# teensyShield1_9.net
KiCad netlist of a schematic drawn in EAGLE
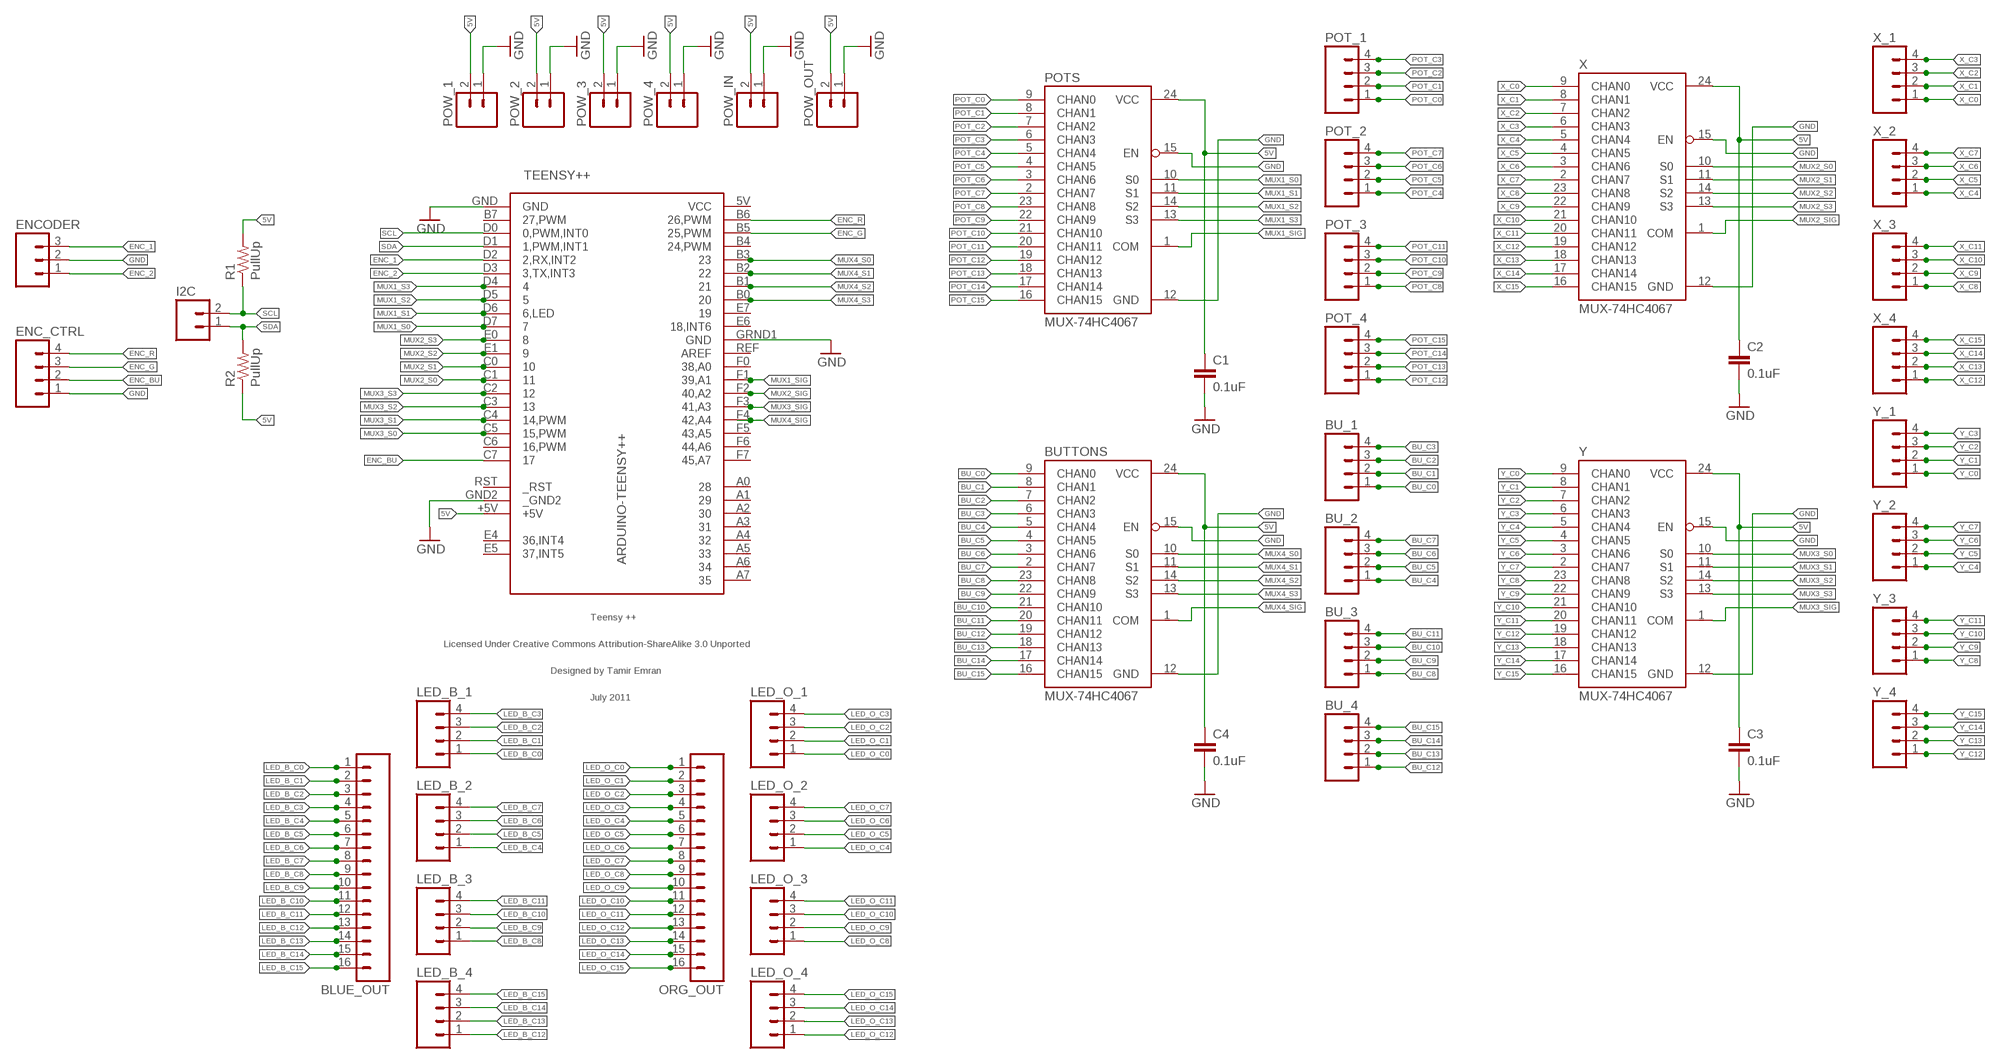
[diagram p0: schematic, sheet 1]

(export (version "E")
  (design (tool "Eeschema 10.0.6"))
  (components
    (comp (ref "BLUE_OUT")
      (value "M161X16_NO_SILK")
      (footprint "eagle-import:1X16_NO_SILK")
      (libsource (lib "eagle-import") (part "M161X16_NO_SILK"))
    )
    (comp (ref "BUTTONS")
      (value "MUX-74HC4067")
      (footprint "eagle-import:SSOP24")
      (libsource (lib "eagle-import") (part "MUX-74HC4067SMD"))
    )
    (comp (ref "BU_1")
      (value "M04NO_SILK_ALL_ROUND")
      (footprint "eagle-import:1X04_NO_SILK_ALL_ROUND")
      (libsource (lib "eagle-import") (part "M04NO_SILK_ALL_ROUND"))
    )
    (comp (ref "BU_2")
      (value "M04NO_SILK_ALL_ROUND")
      (footprint "eagle-import:1X04_NO_SILK_ALL_ROUND")
      (libsource (lib "eagle-import") (part "M04NO_SILK_ALL_ROUND"))
    )
    (comp (ref "BU_3")
      (value "M04NO_SILK_ALL_ROUND")
      (footprint "eagle-import:1X04_NO_SILK_ALL_ROUND")
      (libsource (lib "eagle-import") (part "M04NO_SILK_ALL_ROUND"))
    )
    (comp (ref "BU_4")
      (value "M04NO_SILK_ALL_ROUND")
      (footprint "eagle-import:1X04_NO_SILK_ALL_ROUND")
      (libsource (lib "eagle-import") (part "M04NO_SILK_ALL_ROUND"))
    )
    (comp (ref "C1")
      (value "0.1uF")
      (footprint "eagle-import:0603")
      (libsource (lib "eagle-import") (part "CAP0603"))
    )
    (comp (ref "C2")
      (value "0.1uF")
      (footprint "eagle-import:0603")
      (libsource (lib "eagle-import") (part "CAP0603"))
    )
    (comp (ref "C3")
      (value "0.1uF")
      (footprint "eagle-import:0603")
      (libsource (lib "eagle-import") (part "CAP0603"))
    )
    (comp (ref "C4")
      (value "0.1uF")
      (footprint "eagle-import:0603")
      (libsource (lib "eagle-import") (part "CAP0603"))
    )
    (comp (ref "ENCODER")
      (value "M031X03_NO_SILK")
      (footprint "eagle-import:1X03_NO_SILK")
      (libsource (lib "eagle-import") (part "M031X03_NO_SILK"))
    )
    (comp (ref "ENC_CTRL")
      (value "M041X04_NO_SILK")
      (footprint "eagle-import:1X04_NO_SILK")
      (libsource (lib "eagle-import") (part "M041X04_NO_SILK"))
    )
    (comp (ref "I2C")
      (value "M02LOCK")
      (footprint "eagle-import:1X02_LOCK")
      (libsource (lib "eagle-import") (part "M02LOCK"))
    )
    (comp (ref "LED_B_1")
      (value "M04NO_SILK_ALL_ROUND")
      (footprint "eagle-import:1X04_NO_SILK_ALL_ROUND")
      (libsource (lib "eagle-import") (part "M04NO_SILK_ALL_ROUND"))
    )
    (comp (ref "LED_B_2")
      (value "M04NO_SILK_ALL_ROUND")
      (footprint "eagle-import:1X04_NO_SILK_ALL_ROUND")
      (libsource (lib "eagle-import") (part "M04NO_SILK_ALL_ROUND"))
    )
    (comp (ref "LED_B_3")
      (value "M04NO_SILK_ALL_ROUND")
      (footprint "eagle-import:1X04_NO_SILK_ALL_ROUND")
      (libsource (lib "eagle-import") (part "M04NO_SILK_ALL_ROUND"))
    )
    (comp (ref "LED_B_4")
      (value "M04NO_SILK_ALL_ROUND")
      (footprint "eagle-import:1X04_NO_SILK_ALL_ROUND")
      (libsource (lib "eagle-import") (part "M04NO_SILK_ALL_ROUND"))
    )
    (comp (ref "LED_O_1")
      (value "M04NO_SILK_ALL_ROUND")
      (footprint "eagle-import:1X04_NO_SILK_ALL_ROUND")
      (libsource (lib "eagle-import") (part "M04NO_SILK_ALL_ROUND"))
    )
    (comp (ref "LED_O_2")
      (value "M04NO_SILK_ALL_ROUND")
      (footprint "eagle-import:1X04_NO_SILK_ALL_ROUND")
      (libsource (lib "eagle-import") (part "M04NO_SILK_ALL_ROUND"))
    )
    (comp (ref "LED_O_3")
      (value "M04NO_SILK_ALL_ROUND")
      (footprint "eagle-import:1X04_NO_SILK_ALL_ROUND")
      (libsource (lib "eagle-import") (part "M04NO_SILK_ALL_ROUND"))
    )
    (comp (ref "LED_O_4")
      (value "M04NO_SILK_ALL_ROUND")
      (footprint "eagle-import:1X04_NO_SILK_ALL_ROUND")
      (libsource (lib "eagle-import") (part "M04NO_SILK_ALL_ROUND"))
    )
    (comp (ref "ORG_OUT")
      (value "M161X16_NO_SILK")
      (footprint "eagle-import:1X16_NO_SILK")
      (libsource (lib "eagle-import") (part "M161X16_NO_SILK"))
    )
    (comp (ref "POTS")
      (value "MUX-74HC4067")
      (footprint "eagle-import:SSOP24")
      (libsource (lib "eagle-import") (part "MUX-74HC4067SMD"))
    )
    (comp (ref "POT_1")
      (value "M04NO_SILK_ALL_ROUND")
      (footprint "eagle-import:1X04_NO_SILK_ALL_ROUND")
      (libsource (lib "eagle-import") (part "M04NO_SILK_ALL_ROUND"))
    )
    (comp (ref "POT_2")
      (value "M04NO_SILK_ALL_ROUND")
      (footprint "eagle-import:1X04_NO_SILK_ALL_ROUND")
      (libsource (lib "eagle-import") (part "M04NO_SILK_ALL_ROUND"))
    )
    (comp (ref "POT_3")
      (value "M04NO_SILK_ALL_ROUND")
      (footprint "eagle-import:1X04_NO_SILK_ALL_ROUND")
      (libsource (lib "eagle-import") (part "M04NO_SILK_ALL_ROUND"))
    )
    (comp (ref "POT_4")
      (value "M04NO_SILK_ALL_ROUND")
      (footprint "eagle-import:1X04_NO_SILK_ALL_ROUND")
      (libsource (lib "eagle-import") (part "M04NO_SILK_ALL_ROUND"))
    )
    (comp (ref "POW_1")
      (value "M02POLAR")
      (footprint "eagle-import:MOLEX-1X2")
      (libsource (lib "eagle-import") (part "M02POLAR"))
    )
    (comp (ref "POW_2")
      (value "M02POLAR")
      (footprint "eagle-import:MOLEX-1X2")
      (libsource (lib "eagle-import") (part "M02POLAR"))
    )
    (comp (ref "POW_3")
      (value "M02POLAR")
      (footprint "eagle-import:MOLEX-1X2")
      (libsource (lib "eagle-import") (part "M02POLAR"))
    )
    (comp (ref "POW_4")
      (value "M02POLAR")
      (footprint "eagle-import:MOLEX-1X2")
      (libsource (lib "eagle-import") (part "M02POLAR"))
    )
    (comp (ref "POW_IN")
      (value "M02POLAR")
      (footprint "eagle-import:MOLEX-1X2")
      (libsource (lib "eagle-import") (part "M02POLAR"))
    )
    (comp (ref "POW_OUT")
      (value "M02POLAR")
      (footprint "eagle-import:MOLEX-1X2")
      (libsource (lib "eagle-import") (part "M02POLAR"))
    )
    (comp (ref "R1")
      (value "PullUp")
      (footprint "eagle-import:AXIAL-0.3")
      (libsource (lib "eagle-import") (part "10KOHM-1/4W5%(PTH)"))
    )
    (comp (ref "R2")
      (value "PullUp")
      (footprint "eagle-import:AXIAL-0.3")
      (libsource (lib "eagle-import") (part "10KOHM-1/4W5%(PTH)"))
    )
    (comp (ref "TEENSY++")
      (value "ARDUINO-TEENSY++")
      (footprint "eagle-import:TEENSY++")
      (libsource (lib "eagle-import") (part "ARDUINO-TEENSY++"))
    )
    (comp (ref "X")
      (value "MUX-74HC4067")
      (footprint "eagle-import:SSOP24")
      (libsource (lib "eagle-import") (part "MUX-74HC4067SMD"))
    )
    (comp (ref "X_1")
      (value "M04NO_SILK_ALL_ROUND")
      (footprint "eagle-import:1X04_NO_SILK_ALL_ROUND")
      (libsource (lib "eagle-import") (part "M04NO_SILK_ALL_ROUND"))
    )
    (comp (ref "X_2")
      (value "M04NO_SILK_ALL_ROUND")
      (footprint "eagle-import:1X04_NO_SILK_ALL_ROUND")
      (libsource (lib "eagle-import") (part "M04NO_SILK_ALL_ROUND"))
    )
    (comp (ref "X_3")
      (value "M04NO_SILK_ALL_ROUND")
      (footprint "eagle-import:1X04_NO_SILK_ALL_ROUND")
      (libsource (lib "eagle-import") (part "M04NO_SILK_ALL_ROUND"))
    )
    (comp (ref "X_4")
      (value "M04NO_SILK_ALL_ROUND")
      (footprint "eagle-import:1X04_NO_SILK_ALL_ROUND")
      (libsource (lib "eagle-import") (part "M04NO_SILK_ALL_ROUND"))
    )
    (comp (ref "Y")
      (value "MUX-74HC4067")
      (footprint "eagle-import:SSOP24")
      (libsource (lib "eagle-import") (part "MUX-74HC4067SMD"))
    )
    (comp (ref "Y_1")
      (value "M04NO_SILK_ALL_ROUND")
      (footprint "eagle-import:1X04_NO_SILK_ALL_ROUND")
      (libsource (lib "eagle-import") (part "M04NO_SILK_ALL_ROUND"))
    )
    (comp (ref "Y_2")
      (value "M04NO_SILK_ALL_ROUND")
      (footprint "eagle-import:1X04_NO_SILK_ALL_ROUND")
      (libsource (lib "eagle-import") (part "M04NO_SILK_ALL_ROUND"))
    )
    (comp (ref "Y_3")
      (value "M04NO_SILK_ALL_ROUND")
      (footprint "eagle-import:1X04_NO_SILK_ALL_ROUND")
      (libsource (lib "eagle-import") (part "M04NO_SILK_ALL_ROUND"))
    )
    (comp (ref "Y_4")
      (value "M04NO_SILK_ALL_ROUND")
      (footprint "eagle-import:1X04_NO_SILK_ALL_ROUND")
      (libsource (lib "eagle-import") (part "M04NO_SILK_ALL_ROUND"))
    )
  )
  (nets
    (net (code "1") (name "/VCC") (class "Default")
      (node (ref "TEENSY++") (pin "5V") (pinfunction "VCC_5V") (pintype "power_in"))
    )
    (net (code "2") (name "5V") (class "Default")
      (node (ref "BUTTONS") (pin "24") (pinfunction "VCC_24") (pintype "bidirectional"))
      (node (ref "C1") (pin "1") (pinfunction "1_1") (pintype "passive"))
      (node (ref "C2") (pin "1") (pinfunction "1_1") (pintype "passive"))
      (node (ref "C3") (pin "1") (pinfunction "1_1") (pintype "passive"))
      (node (ref "C4") (pin "1") (pinfunction "1_1") (pintype "passive"))
      (node (ref "POTS") (pin "24") (pinfunction "VCC_24") (pintype "bidirectional"))
      (node (ref "POW_1") (pin "2") (pinfunction "2_2") (pintype "passive"))
      (node (ref "POW_2") (pin "2") (pinfunction "2_2") (pintype "passive"))
      (node (ref "POW_3") (pin "2") (pinfunction "2_2") (pintype "passive"))
      (node (ref "POW_4") (pin "2") (pinfunction "2_2") (pintype "passive"))
      (node (ref "POW_IN") (pin "2") (pinfunction "2_2") (pintype "passive"))
      (node (ref "POW_OUT") (pin "2") (pinfunction "2_2") (pintype "passive"))
      (node (ref "R1") (pin "P$2") (pinfunction "2_P$2") (pintype "passive"))
      (node (ref "R2") (pin "P$1") (pinfunction "1_P$1") (pintype "passive"))
      (node (ref "TEENSY++") (pin "+5V") (pinfunction "+5V_+5V") (pintype "power_in"))
      (node (ref "X") (pin "24") (pinfunction "VCC_24") (pintype "bidirectional"))
      (node (ref "Y") (pin "24") (pinfunction "VCC_24") (pintype "bidirectional"))
    )
    (net (code "3") (name "BU_C0") (class "Default")
      (node (ref "BUTTONS") (pin "9") (pinfunction "CHAN0_9") (pintype "bidirectional"))
      (node (ref "BU_1") (pin "1") (pinfunction "1_1") (pintype "passive"))
    )
    (net (code "4") (name "BU_C1") (class "Default")
      (node (ref "BUTTONS") (pin "8") (pinfunction "CHAN1_8") (pintype "bidirectional"))
      (node (ref "BU_1") (pin "2") (pinfunction "2_2") (pintype "passive"))
    )
    (net (code "5") (name "BU_C2") (class "Default")
      (node (ref "BUTTONS") (pin "7") (pinfunction "CHAN2_7") (pintype "bidirectional"))
      (node (ref "BU_1") (pin "3") (pinfunction "3_3") (pintype "passive"))
    )
    (net (code "6") (name "BU_C3") (class "Default")
      (node (ref "BUTTONS") (pin "6") (pinfunction "CHAN3_6") (pintype "bidirectional"))
      (node (ref "BU_1") (pin "4") (pinfunction "4_4") (pintype "passive"))
    )
    (net (code "7") (name "BU_C4") (class "Default")
      (node (ref "BUTTONS") (pin "5") (pinfunction "CHAN4_5") (pintype "bidirectional"))
      (node (ref "BU_2") (pin "1") (pinfunction "1_1") (pintype "passive"))
    )
    (net (code "8") (name "BU_C5") (class "Default")
      (node (ref "BUTTONS") (pin "4") (pinfunction "CHAN5_4") (pintype "bidirectional"))
      (node (ref "BU_2") (pin "2") (pinfunction "2_2") (pintype "passive"))
    )
    (net (code "9") (name "BU_C6") (class "Default")
      (node (ref "BUTTONS") (pin "3") (pinfunction "CHAN6_3") (pintype "bidirectional"))
      (node (ref "BU_2") (pin "3") (pinfunction "3_3") (pintype "passive"))
    )
    (net (code "10") (name "BU_C7") (class "Default")
      (node (ref "BUTTONS") (pin "2") (pinfunction "CHAN7_2") (pintype "bidirectional"))
      (node (ref "BU_2") (pin "4") (pinfunction "4_4") (pintype "passive"))
    )
    (net (code "11") (name "BU_C8") (class "Default")
      (node (ref "BUTTONS") (pin "23") (pinfunction "CHAN8_23") (pintype "bidirectional"))
      (node (ref "BU_3") (pin "1") (pinfunction "1_1") (pintype "passive"))
    )
    (net (code "12") (name "BU_C9") (class "Default")
      (node (ref "BUTTONS") (pin "22") (pinfunction "CHAN9_22") (pintype "bidirectional"))
      (node (ref "BU_3") (pin "2") (pinfunction "2_2") (pintype "passive"))
    )
    (net (code "13") (name "BU_C10") (class "Default")
      (node (ref "BUTTONS") (pin "21") (pinfunction "CHAN10_21") (pintype "bidirectional"))
      (node (ref "BU_3") (pin "3") (pinfunction "3_3") (pintype "passive"))
    )
    (net (code "14") (name "BU_C11") (class "Default")
      (node (ref "BUTTONS") (pin "20") (pinfunction "CHAN11_20") (pintype "bidirectional"))
      (node (ref "BU_3") (pin "4") (pinfunction "4_4") (pintype "passive"))
    )
    (net (code "15") (name "BU_C12") (class "Default")
      (node (ref "BUTTONS") (pin "19") (pinfunction "CHAN12_19") (pintype "bidirectional"))
      (node (ref "BU_4") (pin "1") (pinfunction "1_1") (pintype "passive"))
    )
    (net (code "16") (name "BU_C13") (class "Default")
      (node (ref "BUTTONS") (pin "18") (pinfunction "CHAN13_18") (pintype "bidirectional"))
      (node (ref "BU_4") (pin "2") (pinfunction "2_2") (pintype "passive"))
    )
    (net (code "17") (name "BU_C14") (class "Default")
      (node (ref "BUTTONS") (pin "17") (pinfunction "CHAN14_17") (pintype "bidirectional"))
      (node (ref "BU_4") (pin "3") (pinfunction "3_3") (pintype "passive"))
    )
    (net (code "18") (name "BU_C15") (class "Default")
      (node (ref "BUTTONS") (pin "16") (pinfunction "CHAN15_16") (pintype "bidirectional"))
      (node (ref "BU_4") (pin "4") (pinfunction "4_4") (pintype "passive"))
    )
    (net (code "19") (name "ENC_1") (class "Default")
      (node (ref "ENCODER") (pin "3") (pinfunction "3_3") (pintype "passive"))
      (node (ref "TEENSY++") (pin "D2") (pinfunction "2,RX,INT2_D2") (pintype "bidirectional"))
    )
    (net (code "20") (name "ENC_2") (class "Default")
      (node (ref "ENCODER") (pin "1") (pinfunction "1_1") (pintype "passive"))
      (node (ref "TEENSY++") (pin "D3") (pinfunction "3,TX,INT3_D3") (pintype "bidirectional"))
    )
    (net (code "21") (name "ENC_BU") (class "Default")
      (node (ref "ENC_CTRL") (pin "2") (pinfunction "2_2") (pintype "passive"))
      (node (ref "TEENSY++") (pin "C7") (pinfunction "17_C7") (pintype "bidirectional"))
    )
    (net (code "22") (name "ENC_G") (class "Default")
      (node (ref "ENC_CTRL") (pin "3") (pinfunction "3_3") (pintype "passive"))
      (node (ref "TEENSY++") (pin "B5") (pinfunction "25,PWM_B5") (pintype "bidirectional"))
    )
    (net (code "23") (name "ENC_R") (class "Default")
      (node (ref "ENC_CTRL") (pin "4") (pinfunction "4_4") (pintype "passive"))
      (node (ref "TEENSY++") (pin "B6") (pinfunction "26,PWM_B6") (pintype "bidirectional"))
    )
    (net (code "24") (name "GND") (class "Default")
      (node (ref "BUTTONS") (pin "12") (pinfunction "GND_12") (pintype "bidirectional"))
      (node (ref "BUTTONS") (pin "15") (pinfunction "EN_15") (pintype "input"))
      (node (ref "C1") (pin "2") (pinfunction "2_2") (pintype "passive"))
      (node (ref "C2") (pin "2") (pinfunction "2_2") (pintype "passive"))
      (node (ref "C3") (pin "2") (pinfunction "2_2") (pintype "passive"))
      (node (ref "C4") (pin "2") (pinfunction "2_2") (pintype "passive"))
      (node (ref "ENCODER") (pin "2") (pinfunction "2_2") (pintype "passive"))
      (node (ref "ENC_CTRL") (pin "1") (pinfunction "1_1") (pintype "passive"))
      (node (ref "POTS") (pin "12") (pinfunction "GND_12") (pintype "bidirectional"))
      (node (ref "POTS") (pin "15") (pinfunction "EN_15") (pintype "input"))
      (node (ref "POW_1") (pin "1") (pinfunction "1_1") (pintype "passive"))
      (node (ref "POW_2") (pin "1") (pinfunction "1_1") (pintype "passive"))
      (node (ref "POW_3") (pin "1") (pinfunction "1_1") (pintype "passive"))
      (node (ref "POW_4") (pin "1") (pinfunction "1_1") (pintype "passive"))
      (node (ref "POW_IN") (pin "1") (pinfunction "1_1") (pintype "passive"))
      (node (ref "POW_OUT") (pin "1") (pinfunction "1_1") (pintype "passive"))
      (node (ref "TEENSY++") (pin "GND") (pinfunction "GND_GND") (pintype "power_in"))
      (node (ref "TEENSY++") (pin "GND2") (pinfunction "_GND2_GND2") (pintype "power_in"))
      (node (ref "TEENSY++") (pin "GRND1") (pinfunction "GND_GRND1") (pintype "power_in"))
      (node (ref "X") (pin "12") (pinfunction "GND_12") (pintype "bidirectional"))
      (node (ref "X") (pin "15") (pinfunction "EN_15") (pintype "input"))
      (node (ref "Y") (pin "12") (pinfunction "GND_12") (pintype "bidirectional"))
      (node (ref "Y") (pin "15") (pinfunction "EN_15") (pintype "input"))
    )
    (net (code "25") (name "LED_B_C0") (class "Default")
      (node (ref "BLUE_OUT") (pin "1") (pinfunction "1_1") (pintype "passive"))
      (node (ref "LED_B_1") (pin "1") (pinfunction "1_1") (pintype "passive"))
    )
    (net (code "26") (name "LED_B_C1") (class "Default")
      (node (ref "BLUE_OUT") (pin "2") (pinfunction "2_2") (pintype "passive"))
      (node (ref "LED_B_1") (pin "2") (pinfunction "2_2") (pintype "passive"))
    )
    (net (code "27") (name "LED_B_C2") (class "Default")
      (node (ref "BLUE_OUT") (pin "3") (pinfunction "3_3") (pintype "passive"))
      (node (ref "LED_B_1") (pin "3") (pinfunction "3_3") (pintype "passive"))
    )
    (net (code "28") (name "LED_B_C3") (class "Default")
      (node (ref "BLUE_OUT") (pin "4") (pinfunction "4_4") (pintype "passive"))
      (node (ref "LED_B_1") (pin "4") (pinfunction "4_4") (pintype "passive"))
    )
    (net (code "29") (name "LED_B_C4") (class "Default")
      (node (ref "BLUE_OUT") (pin "5") (pinfunction "5_5") (pintype "passive"))
      (node (ref "LED_B_2") (pin "1") (pinfunction "1_1") (pintype "passive"))
    )
    (net (code "30") (name "LED_B_C5") (class "Default")
      (node (ref "BLUE_OUT") (pin "6") (pinfunction "6_6") (pintype "passive"))
      (node (ref "LED_B_2") (pin "2") (pinfunction "2_2") (pintype "passive"))
    )
    (net (code "31") (name "LED_B_C6") (class "Default")
      (node (ref "BLUE_OUT") (pin "7") (pinfunction "7_7") (pintype "passive"))
      (node (ref "LED_B_2") (pin "3") (pinfunction "3_3") (pintype "passive"))
    )
    (net (code "32") (name "LED_B_C7") (class "Default")
      (node (ref "BLUE_OUT") (pin "8") (pinfunction "8_8") (pintype "passive"))
      (node (ref "LED_B_2") (pin "4") (pinfunction "4_4") (pintype "passive"))
    )
    (net (code "33") (name "LED_B_C8") (class "Default")
      (node (ref "BLUE_OUT") (pin "9") (pinfunction "9_9") (pintype "passive"))
      (node (ref "LED_B_3") (pin "1") (pinfunction "1_1") (pintype "passive"))
    )
    (net (code "34") (name "LED_B_C9") (class "Default")
      (node (ref "BLUE_OUT") (pin "10") (pinfunction "10_10") (pintype "passive"))
      (node (ref "LED_B_3") (pin "2") (pinfunction "2_2") (pintype "passive"))
    )
    (net (code "35") (name "LED_B_C10") (class "Default")
      (node (ref "BLUE_OUT") (pin "11") (pinfunction "11_11") (pintype "passive"))
      (node (ref "LED_B_3") (pin "3") (pinfunction "3_3") (pintype "passive"))
    )
    (net (code "36") (name "LED_B_C11") (class "Default")
      (node (ref "BLUE_OUT") (pin "12") (pinfunction "12_12") (pintype "passive"))
      (node (ref "LED_B_3") (pin "4") (pinfunction "4_4") (pintype "passive"))
    )
    (net (code "37") (name "LED_B_C12") (class "Default")
      (node (ref "BLUE_OUT") (pin "13") (pinfunction "13_13") (pintype "passive"))
      (node (ref "LED_B_4") (pin "1") (pinfunction "1_1") (pintype "passive"))
    )
    (net (code "38") (name "LED_B_C13") (class "Default")
      (node (ref "BLUE_OUT") (pin "14") (pinfunction "14_14") (pintype "passive"))
      (node (ref "LED_B_4") (pin "2") (pinfunction "2_2") (pintype "passive"))
    )
    (net (code "39") (name "LED_B_C14") (class "Default")
      (node (ref "BLUE_OUT") (pin "15") (pinfunction "15_15") (pintype "passive"))
      (node (ref "LED_B_4") (pin "3") (pinfunction "3_3") (pintype "passive"))
    )
    (net (code "40") (name "LED_B_C15") (class "Default")
      (node (ref "BLUE_OUT") (pin "16") (pinfunction "16_16") (pintype "passive"))
      (node (ref "LED_B_4") (pin "4") (pinfunction "4_4") (pintype "passive"))
    )
    (net (code "41") (name "LED_O_C0") (class "Default")
      (node (ref "LED_O_1") (pin "1") (pinfunction "1_1") (pintype "passive"))
      (node (ref "ORG_OUT") (pin "1") (pinfunction "1_1") (pintype "passive"))
    )
    (net (code "42") (name "LED_O_C1") (class "Default")
      (node (ref "LED_O_1") (pin "2") (pinfunction "2_2") (pintype "passive"))
      (node (ref "ORG_OUT") (pin "2") (pinfunction "2_2") (pintype "passive"))
    )
    (net (code "43") (name "LED_O_C2") (class "Default")
      (node (ref "LED_O_1") (pin "3") (pinfunction "3_3") (pintype "passive"))
      (node (ref "ORG_OUT") (pin "3") (pinfunction "3_3") (pintype "passive"))
    )
    (net (code "44") (name "LED_O_C3") (class "Default")
      (node (ref "LED_O_1") (pin "4") (pinfunction "4_4") (pintype "passive"))
      (node (ref "ORG_OUT") (pin "4") (pinfunction "4_4") (pintype "passive"))
    )
    (net (code "45") (name "LED_O_C4") (class "Default")
      (node (ref "LED_O_2") (pin "1") (pinfunction "1_1") (pintype "passive"))
      (node (ref "ORG_OUT") (pin "5") (pinfunction "5_5") (pintype "passive"))
    )
    (net (code "46") (name "LED_O_C5") (class "Default")
      (node (ref "LED_O_2") (pin "2") (pinfunction "2_2") (pintype "passive"))
      (node (ref "ORG_OUT") (pin "6") (pinfunction "6_6") (pintype "passive"))
    )
    (net (code "47") (name "LED_O_C6") (class "Default")
      (node (ref "LED_O_2") (pin "3") (pinfunction "3_3") (pintype "passive"))
      (node (ref "ORG_OUT") (pin "7") (pinfunction "7_7") (pintype "passive"))
    )
    (net (code "48") (name "LED_O_C7") (class "Default")
      (node (ref "LED_O_2") (pin "4") (pinfunction "4_4") (pintype "passive"))
      (node (ref "ORG_OUT") (pin "8") (pinfunction "8_8") (pintype "passive"))
    )
    (net (code "49") (name "LED_O_C8") (class "Default")
      (node (ref "LED_O_3") (pin "1") (pinfunction "1_1") (pintype "passive"))
      (node (ref "ORG_OUT") (pin "9") (pinfunction "9_9") (pintype "passive"))
    )
    (net (code "50") (name "LED_O_C9") (class "Default")
      (node (ref "LED_O_3") (pin "2") (pinfunction "2_2") (pintype "passive"))
      (node (ref "ORG_OUT") (pin "10") (pinfunction "10_10") (pintype "passive"))
    )
    (net (code "51") (name "LED_O_C10") (class "Default")
      (node (ref "LED_O_3") (pin "3") (pinfunction "3_3") (pintype "passive"))
      (node (ref "ORG_OUT") (pin "11") (pinfunction "11_11") (pintype "passive"))
    )
    (net (code "52") (name "LED_O_C11") (class "Default")
      (node (ref "LED_O_3") (pin "4") (pinfunction "4_4") (pintype "passive"))
      (node (ref "ORG_OUT") (pin "12") (pinfunction "12_12") (pintype "passive"))
    )
    (net (code "53") (name "LED_O_C12") (class "Default")
      (node (ref "LED_O_4") (pin "1") (pinfunction "1_1") (pintype "passive"))
      (node (ref "ORG_OUT") (pin "13") (pinfunction "13_13") (pintype "passive"))
    )
    (net (code "54") (name "LED_O_C13") (class "Default")
      (node (ref "LED_O_4") (pin "2") (pinfunction "2_2") (pintype "passive"))
      (node (ref "ORG_OUT") (pin "14") (pinfunction "14_14") (pintype "passive"))
    )
    (net (code "55") (name "LED_O_C14") (class "Default")
      (node (ref "LED_O_4") (pin "3") (pinfunction "3_3") (pintype "passive"))
      (node (ref "ORG_OUT") (pin "15") (pinfunction "15_15") (pintype "passive"))
    )
    (net (code "56") (name "LED_O_C15") (class "Default")
      (node (ref "LED_O_4") (pin "4") (pinfunction "4_4") (pintype "passive"))
      (node (ref "ORG_OUT") (pin "16") (pinfunction "16_16") (pintype "passive"))
    )
    (net (code "57") (name "MUX1_S0") (class "Default")
      (node (ref "POTS") (pin "10") (pinfunction "S0_10") (pintype "input"))
      (node (ref "TEENSY++") (pin "D7") (pinfunction "7_D7") (pintype "bidirectional"))
    )
    (net (code "58") (name "MUX1_S1") (class "Default")
      (node (ref "POTS") (pin "11") (pinfunction "S1_11") (pintype "input"))
      (node (ref "TEENSY++") (pin "D6") (pinfunction "6,LED_D6") (pintype "bidirectional"))
    )
    (net (code "59") (name "MUX1_S2") (class "Default")
      (node (ref "POTS") (pin "14") (pinfunction "S2_14") (pintype "input"))
      (node (ref "TEENSY++") (pin "D5") (pinfunction "5_D5") (pintype "bidirectional"))
    )
    (net (code "60") (name "MUX1_S3") (class "Default")
      (node (ref "POTS") (pin "13") (pinfunction "S3_13") (pintype "input"))
      (node (ref "TEENSY++") (pin "D4") (pinfunction "4_D4") (pintype "bidirectional"))
    )
    (net (code "61") (name "MUX1_SIG") (class "Default")
      (node (ref "POTS") (pin "1") (pinfunction "COM_1") (pintype "bidirectional"))
      (node (ref "TEENSY++") (pin "F1") (pinfunction "39,A1_F1") (pintype "bidirectional"))
    )
    (net (code "62") (name "MUX2_S0") (class "Default")
      (node (ref "TEENSY++") (pin "C1") (pinfunction "11_C1") (pintype "bidirectional"))
      (node (ref "X") (pin "10") (pinfunction "S0_10") (pintype "input"))
    )
    (net (code "63") (name "MUX2_S1") (class "Default")
      (node (ref "TEENSY++") (pin "C0") (pinfunction "10_C0") (pintype "bidirectional"))
      (node (ref "X") (pin "11") (pinfunction "S1_11") (pintype "input"))
    )
    (net (code "64") (name "MUX2_S2") (class "Default")
      (node (ref "TEENSY++") (pin "E1") (pinfunction "9_E1") (pintype "bidirectional"))
      (node (ref "X") (pin "14") (pinfunction "S2_14") (pintype "input"))
    )
    (net (code "65") (name "MUX2_S3") (class "Default")
      (node (ref "TEENSY++") (pin "E0") (pinfunction "8_E0") (pintype "bidirectional"))
      (node (ref "X") (pin "13") (pinfunction "S3_13") (pintype "input"))
    )
    (net (code "66") (name "MUX2_SIG") (class "Default")
      (node (ref "TEENSY++") (pin "F2") (pinfunction "40,A2_F2") (pintype "bidirectional"))
      (node (ref "X") (pin "1") (pinfunction "COM_1") (pintype "bidirectional"))
    )
    (net (code "67") (name "MUX3_S0") (class "Default")
      (node (ref "TEENSY++") (pin "C5") (pinfunction "15,PWM_C5") (pintype "bidirectional"))
      (node (ref "Y") (pin "10") (pinfunction "S0_10") (pintype "input"))
    )
    (net (code "68") (name "MUX3_S1") (class "Default")
      (node (ref "TEENSY++") (pin "C4") (pinfunction "14,PWM_C4") (pintype "bidirectional"))
      (node (ref "Y") (pin "11") (pinfunction "S1_11") (pintype "input"))
    )
    (net (code "69") (name "MUX3_S2") (class "Default")
      (node (ref "TEENSY++") (pin "C3") (pinfunction "13_C3") (pintype "bidirectional"))
      (node (ref "Y") (pin "14") (pinfunction "S2_14") (pintype "input"))
    )
    (net (code "70") (name "MUX3_S3") (class "Default")
      (node (ref "TEENSY++") (pin "C2") (pinfunction "12_C2") (pintype "bidirectional"))
      (node (ref "Y") (pin "13") (pinfunction "S3_13") (pintype "input"))
    )
    (net (code "71") (name "MUX3_SIG") (class "Default")
      (node (ref "TEENSY++") (pin "F3") (pinfunction "41,A3_F3") (pintype "bidirectional"))
      (node (ref "Y") (pin "1") (pinfunction "COM_1") (pintype "bidirectional"))
    )
    (net (code "72") (name "MUX4_S0") (class "Default")
      (node (ref "BUTTONS") (pin "10") (pinfunction "S0_10") (pintype "input"))
      (node (ref "TEENSY++") (pin "B3") (pinfunction "23_B3") (pintype "bidirectional"))
    )
    (net (code "73") (name "MUX4_S1") (class "Default")
      (node (ref "BUTTONS") (pin "11") (pinfunction "S1_11") (pintype "input"))
      (node (ref "TEENSY++") (pin "B2") (pinfunction "22_B2") (pintype "bidirectional"))
    )
    (net (code "74") (name "MUX4_S2") (class "Default")
      (node (ref "BUTTONS") (pin "14") (pinfunction "S2_14") (pintype "input"))
      (node (ref "TEENSY++") (pin "B1") (pinfunction "21_B1") (pintype "bidirectional"))
    )
    (net (code "75") (name "MUX4_S3") (class "Default")
      (node (ref "BUTTONS") (pin "13") (pinfunction "S3_13") (pintype "input"))
      (node (ref "TEENSY++") (pin "B0") (pinfunction "20_B0") (pintype "bidirectional"))
    )
    (net (code "76") (name "MUX4_SIG") (class "Default")
      (node (ref "BUTTONS") (pin "1") (pinfunction "COM_1") (pintype "bidirectional"))
      (node (ref "TEENSY++") (pin "F4") (pinfunction "42,A4_F4") (pintype "bidirectional"))
    )
    (net (code "77") (name "POT_C0") (class "Default")
      (node (ref "POTS") (pin "9") (pinfunction "CHAN0_9") (pintype "bidirectional"))
      (node (ref "POT_1") (pin "1") (pinfunction "1_1") (pintype "passive"))
    )
    (net (code "78") (name "POT_C1") (class "Default")
      (node (ref "POTS") (pin "8") (pinfunction "CHAN1_8") (pintype "bidirectional"))
      (node (ref "POT_1") (pin "2") (pinfunction "2_2") (pintype "passive"))
    )
    (net (code "79") (name "POT_C2") (class "Default")
      (node (ref "POTS") (pin "7") (pinfunction "CHAN2_7") (pintype "bidirectional"))
      (node (ref "POT_1") (pin "3") (pinfunction "3_3") (pintype "passive"))
    )
    (net (code "80") (name "POT_C3") (class "Default")
      (node (ref "POTS") (pin "6") (pinfunction "CHAN3_6") (pintype "bidirectional"))
      (node (ref "POT_1") (pin "4") (pinfunction "4_4") (pintype "passive"))
    )
    (net (code "81") (name "POT_C4") (class "Default")
      (node (ref "POTS") (pin "5") (pinfunction "CHAN4_5") (pintype "bidirectional"))
      (node (ref "POT_2") (pin "1") (pinfunction "1_1") (pintype "passive"))
    )
    (net (code "82") (name "POT_C5") (class "Default")
      (node (ref "POTS") (pin "4") (pinfunction "CHAN5_4") (pintype "bidirectional"))
      (node (ref "POT_2") (pin "2") (pinfunction "2_2") (pintype "passive"))
    )
    (net (code "83") (name "POT_C6") (class "Default")
      (node (ref "POTS") (pin "3") (pinfunction "CHAN6_3") (pintype "bidirectional"))
      (node (ref "POT_2") (pin "3") (pinfunction "3_3") (pintype "passive"))
    )
    (net (code "84") (name "POT_C7") (class "Default")
      (node (ref "POTS") (pin "2") (pinfunction "CHAN7_2") (pintype "bidirectional"))
      (node (ref "POT_2") (pin "4") (pinfunction "4_4") (pintype "passive"))
    )
    (net (code "85") (name "POT_C8") (class "Default")
      (node (ref "POTS") (pin "23") (pinfunction "CHAN8_23") (pintype "bidirectional"))
      (node (ref "POT_3") (pin "1") (pinfunction "1_1") (pintype "passive"))
    )
    (net (code "86") (name "POT_C9") (class "Default")
      (node (ref "POTS") (pin "22") (pinfunction "CHAN9_22") (pintype "bidirectional"))
      (node (ref "POT_3") (pin "2") (pinfunction "2_2") (pintype "passive"))
    )
    (net (code "87") (name "POT_C10") (class "Default")
      (node (ref "POTS") (pin "21") (pinfunction "CHAN10_21") (pintype "bidirectional"))
      (node (ref "POT_3") (pin "3") (pinfunction "3_3") (pintype "passive"))
    )
    (net (code "88") (name "POT_C11") (class "Default")
      (node (ref "POTS") (pin "20") (pinfunction "CHAN11_20") (pintype "bidirectional"))
      (node (ref "POT_3") (pin "4") (pinfunction "4_4") (pintype "passive"))
    )
    (net (code "89") (name "POT_C12") (class "Default")
      (node (ref "POTS") (pin "19") (pinfunction "CHAN12_19") (pintype "bidirectional"))
      (node (ref "POT_4") (pin "1") (pinfunction "1_1") (pintype "passive"))
    )
    (net (code "90") (name "POT_C13") (class "Default")
      (node (ref "POTS") (pin "18") (pinfunction "CHAN13_18") (pintype "bidirectional"))
      (node (ref "POT_4") (pin "2") (pinfunction "2_2") (pintype "passive"))
    )
    (net (code "91") (name "POT_C14") (class "Default")
      (node (ref "POTS") (pin "17") (pinfunction "CHAN14_17") (pintype "bidirectional"))
      (node (ref "POT_4") (pin "3") (pinfunction "3_3") (pintype "passive"))
    )
    (net (code "92") (name "POT_C15") (class "Default")
      (node (ref "POTS") (pin "16") (pinfunction "CHAN15_16") (pintype "bidirectional"))
      (node (ref "POT_4") (pin "4") (pinfunction "4_4") (pintype "passive"))
    )
    (net (code "93") (name "SCL") (class "Default")
      (node (ref "I2C") (pin "2") (pinfunction "2_2") (pintype "passive"))
      (node (ref "R1") (pin "P$1") (pinfunction "1_P$1") (pintype "passive"))
      (node (ref "TEENSY++") (pin "D0") (pinfunction "0,PWM,INT0_D0") (pintype "bidirectional"))
    )
    (net (code "94") (name "SDA") (class "Default")
      (node (ref "I2C") (pin "1") (pinfunction "1_1") (pintype "passive"))
      (node (ref "R2") (pin "P$2") (pinfunction "2_P$2") (pintype "passive"))
      (node (ref "TEENSY++") (pin "D1") (pinfunction "1,PWM,INT1_D1") (pintype "bidirectional"))
    )
    (net (code "95") (name "X_C0") (class "Default")
      (node (ref "X") (pin "9") (pinfunction "CHAN0_9") (pintype "bidirectional"))
      (node (ref "X_1") (pin "1") (pinfunction "1_1") (pintype "passive"))
    )
    (net (code "96") (name "X_C1") (class "Default")
      (node (ref "X") (pin "8") (pinfunction "CHAN1_8") (pintype "bidirectional"))
      (node (ref "X_1") (pin "2") (pinfunction "2_2") (pintype "passive"))
    )
    (net (code "97") (name "X_C2") (class "Default")
      (node (ref "X") (pin "7") (pinfunction "CHAN2_7") (pintype "bidirectional"))
      (node (ref "X_1") (pin "3") (pinfunction "3_3") (pintype "passive"))
    )
    (net (code "98") (name "X_C3") (class "Default")
      (node (ref "X") (pin "6") (pinfunction "CHAN3_6") (pintype "bidirectional"))
      (node (ref "X_1") (pin "4") (pinfunction "4_4") (pintype "passive"))
    )
    (net (code "99") (name "X_C4") (class "Default")
      (node (ref "X") (pin "5") (pinfunction "CHAN4_5") (pintype "bidirectional"))
      (node (ref "X_2") (pin "1") (pinfunction "1_1") (pintype "passive"))
    )
    (net (code "100") (name "X_C5") (class "Default")
      (node (ref "X") (pin "4") (pinfunction "CHAN5_4") (pintype "bidirectional"))
      (node (ref "X_2") (pin "2") (pinfunction "2_2") (pintype "passive"))
    )
    (net (code "101") (name "X_C6") (class "Default")
      (node (ref "X") (pin "3") (pinfunction "CHAN6_3") (pintype "bidirectional"))
      (node (ref "X_2") (pin "3") (pinfunction "3_3") (pintype "passive"))
    )
    (net (code "102") (name "X_C7") (class "Default")
      (node (ref "X") (pin "2") (pinfunction "CHAN7_2") (pintype "bidirectional"))
      (node (ref "X_2") (pin "4") (pinfunction "4_4") (pintype "passive"))
    )
    (net (code "103") (name "X_C8") (class "Default")
      (node (ref "X") (pin "23") (pinfunction "CHAN8_23") (pintype "bidirectional"))
      (node (ref "X_3") (pin "1") (pinfunction "1_1") (pintype "passive"))
    )
    (net (code "104") (name "X_C9") (class "Default")
      (node (ref "X") (pin "22") (pinfunction "CHAN9_22") (pintype "bidirectional"))
      (node (ref "X_3") (pin "2") (pinfunction "2_2") (pintype "passive"))
    )
    (net (code "105") (name "X_C10") (class "Default")
      (node (ref "X") (pin "21") (pinfunction "CHAN10_21") (pintype "bidirectional"))
      (node (ref "X_3") (pin "3") (pinfunction "3_3") (pintype "passive"))
    )
    (net (code "106") (name "X_C11") (class "Default")
      (node (ref "X") (pin "20") (pinfunction "CHAN11_20") (pintype "bidirectional"))
      (node (ref "X_3") (pin "4") (pinfunction "4_4") (pintype "passive"))
    )
    (net (code "107") (name "X_C12") (class "Default")
      (node (ref "X") (pin "19") (pinfunction "CHAN12_19") (pintype "bidirectional"))
      (node (ref "X_4") (pin "1") (pinfunction "1_1") (pintype "passive"))
    )
    (net (code "108") (name "X_C13") (class "Default")
      (node (ref "X") (pin "18") (pinfunction "CHAN13_18") (pintype "bidirectional"))
      (node (ref "X_4") (pin "2") (pinfunction "2_2") (pintype "passive"))
    )
    (net (code "109") (name "X_C14") (class "Default")
      (node (ref "X") (pin "17") (pinfunction "CHAN14_17") (pintype "bidirectional"))
      (node (ref "X_4") (pin "3") (pinfunction "3_3") (pintype "passive"))
    )
    (net (code "110") (name "X_C15") (class "Default")
      (node (ref "X") (pin "16") (pinfunction "CHAN15_16") (pintype "bidirectional"))
      (node (ref "X_4") (pin "4") (pinfunction "4_4") (pintype "passive"))
    )
    (net (code "111") (name "Y_C0") (class "Default")
      (node (ref "Y") (pin "9") (pinfunction "CHAN0_9") (pintype "bidirectional"))
      (node (ref "Y_1") (pin "1") (pinfunction "1_1") (pintype "passive"))
    )
    (net (code "112") (name "Y_C1") (class "Default")
      (node (ref "Y") (pin "8") (pinfunction "CHAN1_8") (pintype "bidirectional"))
      (node (ref "Y_1") (pin "2") (pinfunction "2_2") (pintype "passive"))
    )
    (net (code "113") (name "Y_C2") (class "Default")
      (node (ref "Y") (pin "7") (pinfunction "CHAN2_7") (pintype "bidirectional"))
      (node (ref "Y_1") (pin "3") (pinfunction "3_3") (pintype "passive"))
    )
    (net (code "114") (name "Y_C3") (class "Default")
      (node (ref "Y") (pin "6") (pinfunction "CHAN3_6") (pintype "bidirectional"))
      (node (ref "Y_1") (pin "4") (pinfunction "4_4") (pintype "passive"))
    )
    (net (code "115") (name "Y_C4") (class "Default")
      (node (ref "Y") (pin "5") (pinfunction "CHAN4_5") (pintype "bidirectional"))
      (node (ref "Y_2") (pin "1") (pinfunction "1_1") (pintype "passive"))
    )
    (net (code "116") (name "Y_C5") (class "Default")
      (node (ref "Y") (pin "4") (pinfunction "CHAN5_4") (pintype "bidirectional"))
      (node (ref "Y_2") (pin "2") (pinfunction "2_2") (pintype "passive"))
    )
    (net (code "117") (name "Y_C6") (class "Default")
      (node (ref "Y") (pin "3") (pinfunction "CHAN6_3") (pintype "bidirectional"))
      (node (ref "Y_2") (pin "3") (pinfunction "3_3") (pintype "passive"))
    )
    (net (code "118") (name "Y_C7") (class "Default")
      (node (ref "Y") (pin "2") (pinfunction "CHAN7_2") (pintype "bidirectional"))
      (node (ref "Y_2") (pin "4") (pinfunction "4_4") (pintype "passive"))
    )
    (net (code "119") (name "Y_C8") (class "Default")
      (node (ref "Y") (pin "23") (pinfunction "CHAN8_23") (pintype "bidirectional"))
      (node (ref "Y_3") (pin "1") (pinfunction "1_1") (pintype "passive"))
    )
    (net (code "120") (name "Y_C9") (class "Default")
      (node (ref "Y") (pin "22") (pinfunction "CHAN9_22") (pintype "bidirectional"))
      (node (ref "Y_3") (pin "2") (pinfunction "2_2") (pintype "passive"))
    )
    (net (code "121") (name "Y_C10") (class "Default")
      (node (ref "Y") (pin "21") (pinfunction "CHAN10_21") (pintype "bidirectional"))
      (node (ref "Y_3") (pin "3") (pinfunction "3_3") (pintype "passive"))
    )
    (net (code "122") (name "Y_C11") (class "Default")
      (node (ref "Y") (pin "20") (pinfunction "CHAN11_20") (pintype "bidirectional"))
      (node (ref "Y_3") (pin "4") (pinfunction "4_4") (pintype "passive"))
    )
    (net (code "123") (name "Y_C12") (class "Default")
      (node (ref "Y") (pin "19") (pinfunction "CHAN12_19") (pintype "bidirectional"))
      (node (ref "Y_4") (pin "1") (pinfunction "1_1") (pintype "passive"))
    )
    (net (code "124") (name "Y_C13") (class "Default")
      (node (ref "Y") (pin "18") (pinfunction "CHAN13_18") (pintype "bidirectional"))
      (node (ref "Y_4") (pin "2") (pinfunction "2_2") (pintype "passive"))
    )
    (net (code "125") (name "Y_C14") (class "Default")
      (node (ref "Y") (pin "17") (pinfunction "CHAN14_17") (pintype "bidirectional"))
      (node (ref "Y_4") (pin "3") (pinfunction "3_3") (pintype "passive"))
    )
    (net (code "126") (name "Y_C15") (class "Default")
      (node (ref "Y") (pin "16") (pinfunction "CHAN15_16") (pintype "bidirectional"))
      (node (ref "Y_4") (pin "4") (pinfunction "4_4") (pintype "passive"))
    )
    (net (code "127") (name "unconnected-(TEENSY++-16,PWM-PadC6)") (class "Default")
      (node (ref "TEENSY++") (pin "C6") (pinfunction "16,PWM_C6") (pintype "bidirectional"))
    )
    (net (code "128") (name "unconnected-(TEENSY++-18,INT6-PadE6)") (class "Default")
      (node (ref "TEENSY++") (pin "E6") (pinfunction "18,INT6_E6") (pintype "bidirectional"))
    )
    (net (code "129") (name "unconnected-(TEENSY++-19-PadE7)") (class "Default")
      (node (ref "TEENSY++") (pin "E7") (pinfunction "19_E7") (pintype "bidirectional"))
    )
    (net (code "130") (name "unconnected-(TEENSY++-24,PWM-PadB4)") (class "Default")
      (node (ref "TEENSY++") (pin "B4") (pinfunction "24,PWM_B4") (pintype "bidirectional"))
    )
    (net (code "131") (name "unconnected-(TEENSY++-27,PWM-PadB7)") (class "Default")
      (node (ref "TEENSY++") (pin "B7") (pinfunction "27,PWM_B7") (pintype "bidirectional"))
    )
    (net (code "132") (name "unconnected-(TEENSY++-28-PadA0)") (class "Default")
      (node (ref "TEENSY++") (pin "A0") (pinfunction "28_A0") (pintype "bidirectional"))
    )
    (net (code "133") (name "unconnected-(TEENSY++-29-PadA1)") (class "Default")
      (node (ref "TEENSY++") (pin "A1") (pinfunction "29_A1") (pintype "bidirectional"))
    )
    (net (code "134") (name "unconnected-(TEENSY++-30-PadA2)") (class "Default")
      (node (ref "TEENSY++") (pin "A2") (pinfunction "30_A2") (pintype "bidirectional"))
    )
    (net (code "135") (name "unconnected-(TEENSY++-31-PadA3)") (class "Default")
      (node (ref "TEENSY++") (pin "A3") (pinfunction "31_A3") (pintype "bidirectional"))
    )
    (net (code "136") (name "unconnected-(TEENSY++-32-PadA4)") (class "Default")
      (node (ref "TEENSY++") (pin "A4") (pinfunction "32_A4") (pintype "bidirectional"))
    )
    (net (code "137") (name "unconnected-(TEENSY++-33-PadA5)") (class "Default")
      (node (ref "TEENSY++") (pin "A5") (pinfunction "33_A5") (pintype "bidirectional"))
    )
    (net (code "138") (name "unconnected-(TEENSY++-34-PadA6)") (class "Default")
      (node (ref "TEENSY++") (pin "A6") (pinfunction "34_A6") (pintype "bidirectional"))
    )
    (net (code "139") (name "unconnected-(TEENSY++-35-PadA7)") (class "Default")
      (node (ref "TEENSY++") (pin "A7") (pinfunction "35_A7") (pintype "bidirectional"))
    )
    (net (code "140") (name "unconnected-(TEENSY++-36,INT4-PadE4)") (class "Default")
      (node (ref "TEENSY++") (pin "E4") (pinfunction "36,INT4_E4") (pintype "bidirectional"))
    )
    (net (code "141") (name "unconnected-(TEENSY++-37,INT5-PadE5)") (class "Default")
      (node (ref "TEENSY++") (pin "E5") (pinfunction "37,INT5_E5") (pintype "bidirectional"))
    )
    (net (code "142") (name "unconnected-(TEENSY++-38,A0-PadF0)") (class "Default")
      (node (ref "TEENSY++") (pin "F0") (pinfunction "38,A0_F0") (pintype "bidirectional"))
    )
    (net (code "143") (name "unconnected-(TEENSY++-43,A5-PadF5)") (class "Default")
      (node (ref "TEENSY++") (pin "F5") (pinfunction "43,A5_F5") (pintype "bidirectional"))
    )
    (net (code "144") (name "unconnected-(TEENSY++-44,A6-PadF6)") (class "Default")
      (node (ref "TEENSY++") (pin "F6") (pinfunction "44,A6_F6") (pintype "bidirectional"))
    )
    (net (code "145") (name "unconnected-(TEENSY++-45,A7-PadF7)") (class "Default")
      (node (ref "TEENSY++") (pin "F7") (pinfunction "45,A7_F7") (pintype "bidirectional"))
    )
    (net (code "146") (name "unconnected-(TEENSY++-AREF-PadREF)") (class "Default")
      (node (ref "TEENSY++") (pin "REF") (pinfunction "AREF_REF") (pintype "input"))
    )
    (net (code "147") (name "unconnected-(TEENSY++-_RST-PadRST)") (class "Default")
      (node (ref "TEENSY++") (pin "RST") (pinfunction "_RST_RST") (pintype "input"))
    )
  )
)
